# os20_newenc.net
KiCad netlist of a schematic drawn in EAGLE
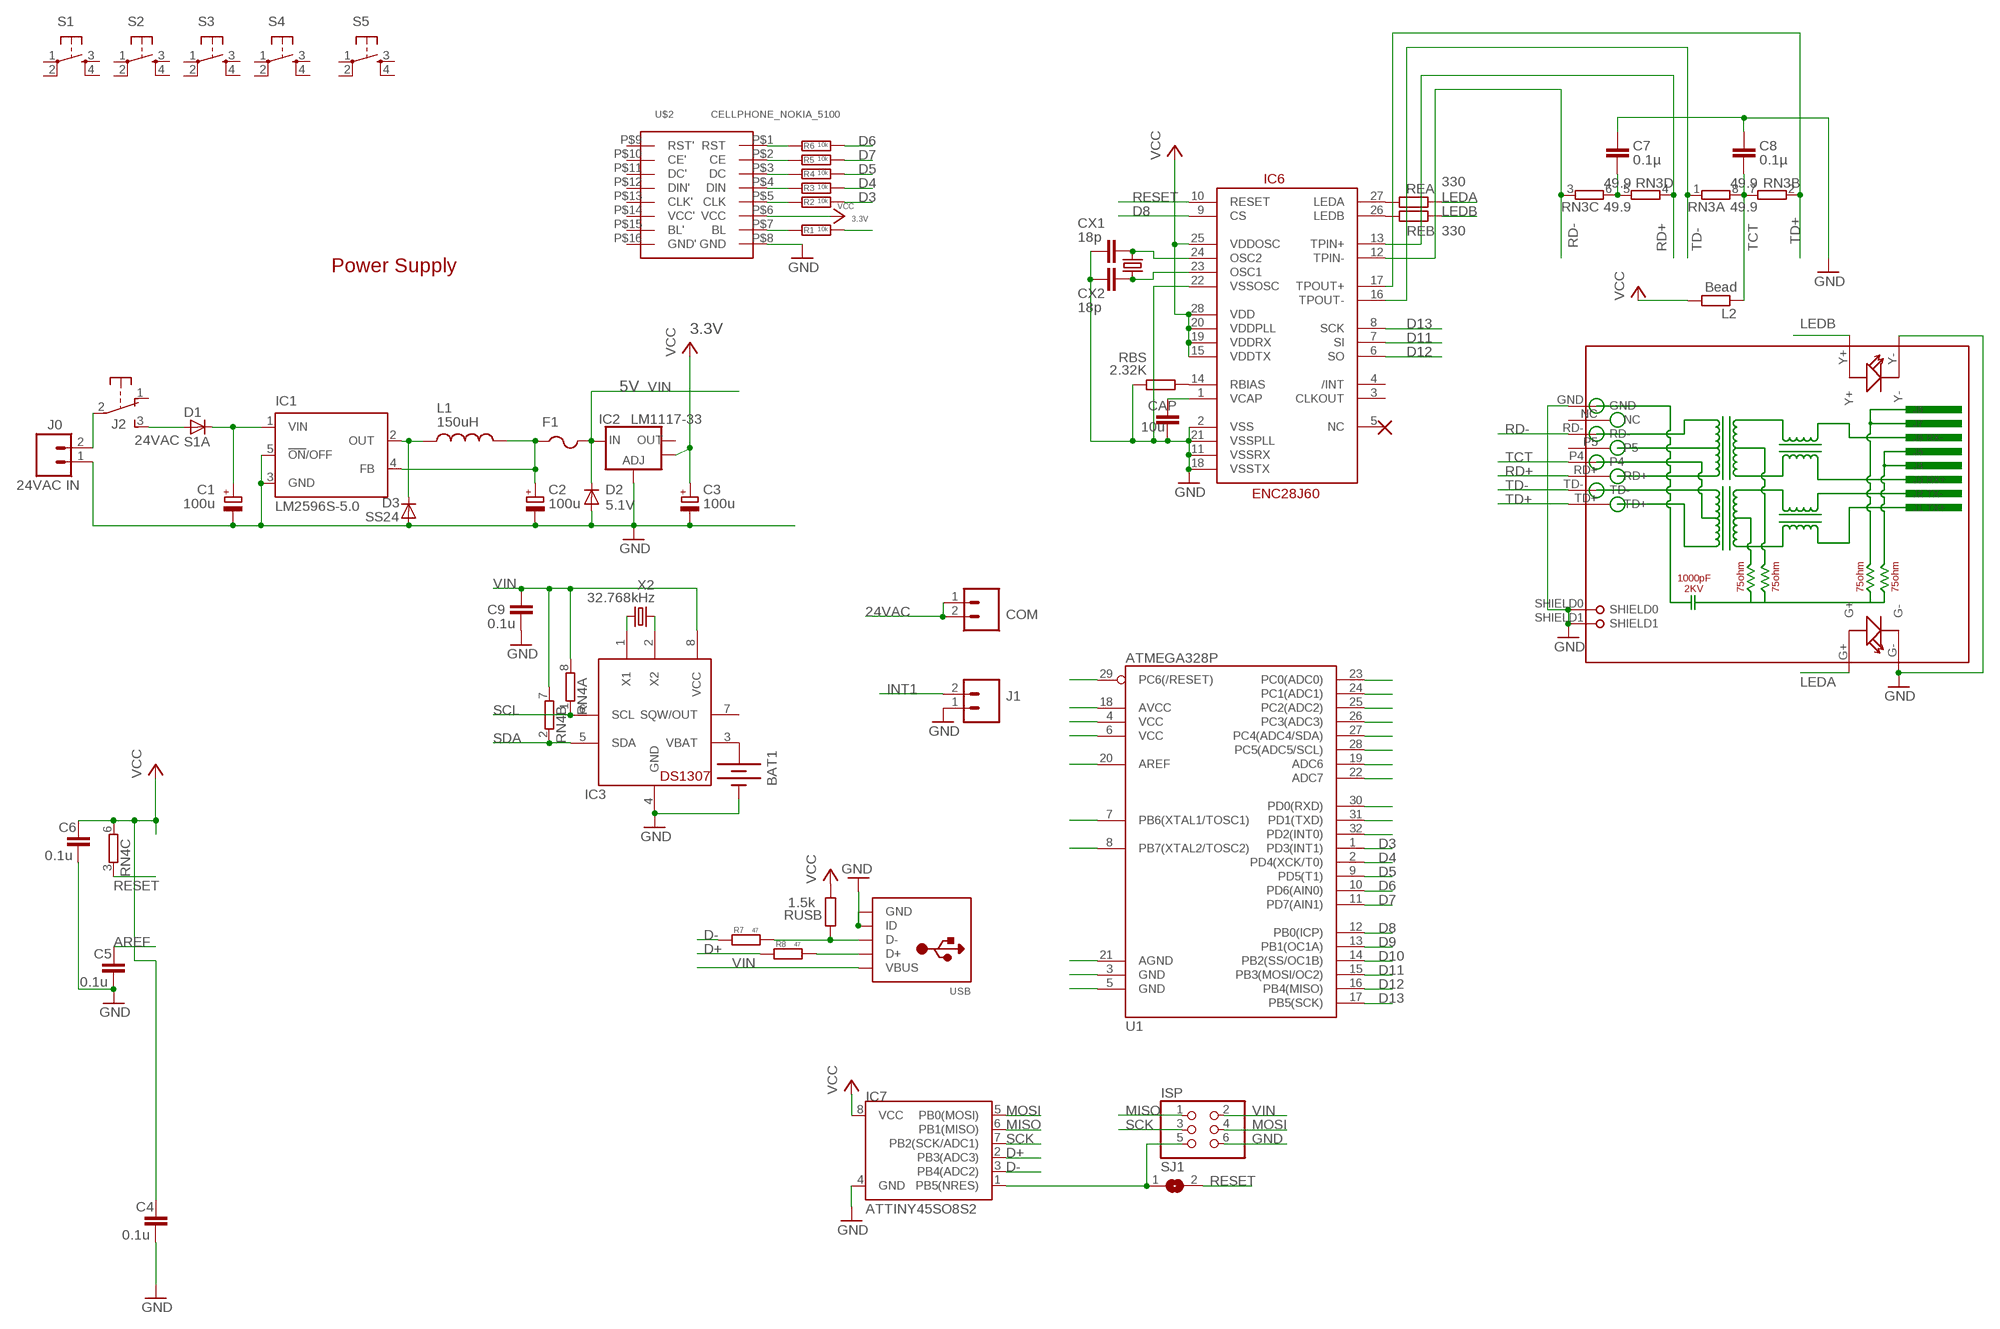
[diagram p0: schematic, sheet 1]

(export (version "E")
  (design (tool "Eeschema 10.0.6"))
  (components
    (comp (ref "BAT1")
      (value "BATTERYBATTERY_12MM_SMT")
      (footprint "eagle-import:BATTCON_12MM_SMT")
      (libsource (lib "eagle-import") (part "BATTERYBATTERY_12MM_SMT"))
    )
    (comp (ref "C1")
      (value "100u")
      (footprint "eagle-import:E3,5-8")
      (libsource (lib "eagle-import") (part "CPOL-EUE3.5-8"))
    )
    (comp (ref "C2")
      (value "100u")
      (footprint "eagle-import:PANASONIC_D")
      (libsource (lib "eagle-import") (part "CPOL-EUD"))
    )
    (comp (ref "C3")
      (value "100u")
      (footprint "eagle-import:PANASONIC_D")
      (libsource (lib "eagle-import") (part "CPOL-EUD"))
    )
    (comp (ref "C4")
      (value "0.1u")
      (footprint "eagle-import:C0805")
      (libsource (lib "eagle-import") (part "C-EUC0805"))
    )
    (comp (ref "C5")
      (value "0.1u")
      (footprint "eagle-import:C0805")
      (libsource (lib "eagle-import") (part "C-EUC0805"))
    )
    (comp (ref "C6")
      (value "0.1u")
      (footprint "eagle-import:C0805")
      (libsource (lib "eagle-import") (part "C-EUC0805"))
    )
    (comp (ref "C7")
      (value "0.1µ")
      (footprint "eagle-import:C0805")
      (libsource (lib "eagle-import") (part "resistor_C-EUC0805"))
    )
    (comp (ref "C8")
      (value "0.1µ")
      (footprint "eagle-import:C0805")
      (libsource (lib "eagle-import") (part "resistor_C-EUC0805"))
    )
    (comp (ref "C9")
      (value "0.1u")
      (footprint "eagle-import:C0805")
      (libsource (lib "eagle-import") (part "C-EUC0805"))
    )
    (comp (ref "CAP")
      (value "10u")
      (footprint "eagle-import:C0805")
      (libsource (lib "eagle-import") (part "resistor_C-EUC0805"))
    )
    (comp (ref "COM")
      (value "M025MM")
      (footprint "eagle-import:SCREWTERMINAL-5MM-2")
      (libsource (lib "eagle-import") (part "M025MM"))
    )
    (comp (ref "CX1")
      (value "18p")
      (footprint "eagle-import:C0805")
      (libsource (lib "eagle-import") (part "resistor_C-EUC0805"))
    )
    (comp (ref "CX2")
      (value "18p")
      (footprint "eagle-import:C0805")
      (libsource (lib "eagle-import") (part "resistor_C-EUC0805"))
    )
    (comp (ref "D1")
      (value "S1A")
      (footprint "eagle-import:DO-214AC")
      (libsource (lib "eagle-import") (part "DIODE-DO-214AC"))
    )
    (comp (ref "D2")
      (value "5.1V")
      (footprint "eagle-import:MINIMELF")
      (libsource (lib "eagle-import") (part "DIODE-MINIMELF"))
    )
    (comp (ref "D3")
      (value "SS24")
      (footprint "eagle-import:DO-214AC")
      (libsource (lib "eagle-import") (part "DIODE-DO-214AC"))
    )
    (comp (ref "F1")
      (value "PTCFUSE-1812")
      (footprint "eagle-import:1812")
      (libsource (lib "eagle-import") (part "PTCFUSE-1812"))
    )
    (comp (ref "IC1")
      (value "LM2596S-5.0")
      (footprint "eagle-import:TO263-5")
      (fields (field (name "MF") "NATIONAL SEMICONDUCTOR") (field (name "MPN") "LM2596S-ADJ/NOPB"))
      (libsource (lib "eagle-import") (part "LM2596S"))
    )
    (comp (ref "IC2")
      (value "LM1117-33")
      (footprint "eagle-import:SOT223")
      (libsource (lib "eagle-import") (part "V_REG_LM1117SOT223"))
    )
    (comp (ref "IC3")
      (value "DS1307")
      (footprint "eagle-import:SO08")
      (libsource (lib "eagle-import") (part "DS1307SOIC"))
    )
    (comp (ref "IC6")
      (value "ENC28J60")
      (footprint "eagle-import:SSOP28DB")
      (libsource (lib "eagle-import") (part "ENC28J60"))
    )
    (comp (ref "IC7")
      (value "ATTINY45SO8S2")
      (footprint "eagle-import:SO8S2")
      (libsource (lib "eagle-import") (part "ATTINY45SO8S2"))
    )
    (comp (ref "ISP")
      (value "PINHD-2X3")
      (footprint "eagle-import:2X03")
      (libsource (lib "eagle-import") (part "PINHD-2X3"))
    )
    (comp (ref "J0")
      (value "24VAC IN")
      (footprint "eagle-import:SCREWTERMINAL-5MM-2")
      (libsource (lib "eagle-import") (part "M025MM"))
    )
    (comp (ref "J1")
      (value "M025MM")
      (footprint "eagle-import:SCREWTERMINAL-5MM-2")
      (libsource (lib "eagle-import") (part "M025MM"))
    )
    (comp (ref "J2")
      (value "EG1206")
      (footprint "eagle-import:EG1206")
      (libsource (lib "eagle-import") (part "EG1206"))
    )
    (comp (ref "L1")
      (value "150uH")
      (footprint "eagle-import:CDRH125")
      (libsource (lib "eagle-import") (part "INDUCTORPWR"))
    )
    (comp (ref "L2")
      (value "Bead")
      (footprint "eagle-import:R0805")
      (libsource (lib "eagle-import") (part "R-EU_R0805"))
    )
    (comp (ref "R1")
      (value "10k")
      (footprint "eagle-import:R0805")
      (libsource (lib "eagle-import") (part "R-EU_R0805"))
    )
    (comp (ref "R2")
      (value "10k")
      (footprint "eagle-import:R0805")
      (libsource (lib "eagle-import") (part "R-EU_R0805"))
    )
    (comp (ref "R3")
      (value "10k")
      (footprint "eagle-import:R0805")
      (libsource (lib "eagle-import") (part "R-EU_R0805"))
    )
    (comp (ref "R4")
      (value "10k")
      (footprint "eagle-import:R0805")
      (libsource (lib "eagle-import") (part "R-EU_R0805"))
    )
    (comp (ref "R5")
      (value "10k")
      (footprint "eagle-import:R0805")
      (libsource (lib "eagle-import") (part "R-EU_R0805"))
    )
    (comp (ref "R6")
      (value "10k")
      (footprint "eagle-import:R0805")
      (libsource (lib "eagle-import") (part "R-EU_R0805"))
    )
    (comp (ref "R7")
      (value "47")
      (footprint "eagle-import:R0805")
      (libsource (lib "eagle-import") (part "R-EU_R0805"))
    )
    (comp (ref "R8")
      (value "47")
      (footprint "eagle-import:R0805")
      (libsource (lib "eagle-import") (part "R-EU_R0805"))
    )
    (comp (ref "RBS")
      (value "2.32K")
      (footprint "eagle-import:R0805")
      (libsource (lib "eagle-import") (part "R-EU_R0805"))
    )
    (comp (ref "REA")
      (value "330")
      (footprint "eagle-import:R0805")
      (libsource (lib "eagle-import") (part "R-EU_R0805"))
    )
    (comp (ref "REB")
      (value "330")
      (footprint "eagle-import:R0805")
      (libsource (lib "eagle-import") (part "R-EU_R0805"))
    )
    (comp (ref "RJ45")
      (value "HR911105A")
      (footprint "eagle-import:HR911105A")
      (libsource (lib "eagle-import") (part "HR911105A"))
    )
    (comp (ref "RN3")
      (value "49.9")
      (footprint "eagle-import:EXB38V")
      (libsource (lib "eagle-import") (part "4R-NEXB38V"))
    )
    (comp (ref "RN4")
      (value "4R-NEXB38V")
      (footprint "eagle-import:EXB38V")
      (libsource (lib "eagle-import") (part "4R-NEXB38V"))
    )
    (comp (ref "RUSB")
      (value "1.5k")
      (footprint "eagle-import:R0805")
      (libsource (lib "eagle-import") (part "R-EU_R0805"))
    )
    (comp (ref "S1")
      (value "TAC_SWITCHPTH")
      (footprint "eagle-import:TACTILE-PTH")
      (libsource (lib "eagle-import") (part "TAC_SWITCHPTH"))
    )
    (comp (ref "S2")
      (value "TAC_SWITCHPTH")
      (footprint "eagle-import:TACTILE-PTH")
      (libsource (lib "eagle-import") (part "TAC_SWITCHPTH"))
    )
    (comp (ref "S3")
      (value "TAC_SWITCHPTH")
      (footprint "eagle-import:TACTILE-PTH")
      (libsource (lib "eagle-import") (part "TAC_SWITCHPTH"))
    )
    (comp (ref "S4")
      (value "TAC_SWITCHPTH")
      (footprint "eagle-import:TACTILE-PTH")
      (libsource (lib "eagle-import") (part "TAC_SWITCHPTH"))
    )
    (comp (ref "S5")
      (value "TAC_SWITCHPTH")
      (footprint "eagle-import:TACTILE-PTH")
      (libsource (lib "eagle-import") (part "TAC_SWITCHPTH"))
    )
    (comp (ref "SJ1") (value "SJ") (footprint "eagle-import:SJ") (libsource (lib "eagle-import") (part "SJ")))
    (comp (ref "U$2")
      (value "CELLPHONE_NOKIA_5100")
      (footprint "eagle-import:CELLPHONE_NOKIA_5100_SPARKFUN")
      (libsource (lib "eagle-import") (part "CELLPHONE_NOKIA_5100"))
    )
    (comp (ref "U1")
      (value "ATMEGA328P")
      (footprint "eagle-import:TQFP32-08")
      (libsource (lib "eagle-import") (part "ATMEGA328_SMT"))
    )
    (comp (ref "USB")
      (value "USBMOLEX")
      (footprint "eagle-import:USB-MINIB-THM-MOLEX")
      (libsource (lib "eagle-import") (part "USBMOLEX"))
    )
    (comp (ref "X1")
      (value "25MHz")
      (footprint "eagle-import:HC49US")
      (libsource (lib "eagle-import") (part "CRYSTALHC49US"))
    )
    (comp (ref "X2")
      (value "32.768kHz")
      (footprint "eagle-import:TC26H")
      (libsource (lib "eagle-import") (part "crystal_CRYSTALTC26H"))
    )
  )
  (nets
    (net (code "1") (name "/24VAC") (class "Default")
      (node (ref "COM") (pin "1") (pinfunction "1_1") (pintype "passive"))
      (node (ref "COM") (pin "2") (pinfunction "2_2") (pintype "passive"))
      (node (ref "D1") (pin "A") (pinfunction "A_A") (pintype "passive"))
      (node (ref "J2") (pin "3") (pinfunction "S_3") (pintype "passive"))
    )
    (net (code "2") (name "/AREF") (class "Default")
      (node (ref "C5") (pin "1") (pinfunction "1_1") (pintype "passive"))
    )
    (net (code "3") (name "/D+") (class "Default")
      (node (ref "IC7") (pin "2") (pinfunction "PB3(ADC3)_2") (pintype "bidirectional"))
      (node (ref "R8") (pin "1") (pinfunction "1_1") (pintype "passive"))
    )
    (net (code "4") (name "/D-") (class "Default")
      (node (ref "IC7") (pin "3") (pinfunction "PB4(ADC2)_3") (pintype "bidirectional"))
      (node (ref "R7") (pin "1") (pinfunction "1_1") (pintype "passive"))
    )
    (net (code "5") (name "/D3") (class "Default")
      (node (ref "R2") (pin "2") (pinfunction "2_2") (pintype "passive"))
      (node (ref "U1") (pin "1") (pinfunction "PD3(INT1)_1") (pintype "bidirectional"))
    )
    (net (code "6") (name "/D4") (class "Default")
      (node (ref "R3") (pin "2") (pinfunction "2_2") (pintype "passive"))
      (node (ref "U1") (pin "2") (pinfunction "PD4(XCK/T0)_2") (pintype "bidirectional"))
    )
    (net (code "7") (name "/D5") (class "Default")
      (node (ref "R4") (pin "2") (pinfunction "2_2") (pintype "passive"))
      (node (ref "U1") (pin "9") (pinfunction "PD5(T1)_9") (pintype "bidirectional"))
    )
    (net (code "8") (name "/D6") (class "Default")
      (node (ref "R6") (pin "2") (pinfunction "2_2") (pintype "passive"))
      (node (ref "U1") (pin "10") (pinfunction "PD6(AIN0)_10") (pintype "bidirectional"))
    )
    (net (code "9") (name "/D7") (class "Default")
      (node (ref "R5") (pin "2") (pinfunction "2_2") (pintype "passive"))
      (node (ref "U1") (pin "11") (pinfunction "PD7(AIN1)_11") (pintype "bidirectional"))
    )
    (net (code "10") (name "/D8") (class "Default")
      (node (ref "IC6") (pin "9") (pinfunction "CS_9") (pintype "bidirectional"))
      (node (ref "U1") (pin "12") (pinfunction "PB0(ICP)_12") (pintype "bidirectional"))
    )
    (net (code "11") (name "/D9") (class "Default")
      (node (ref "U1") (pin "13") (pinfunction "PB1(OC1A)_13") (pintype "bidirectional"))
    )
    (net (code "12") (name "/D10") (class "Default")
      (node (ref "U1") (pin "14") (pinfunction "PB2(SS/OC1B)_14") (pintype "bidirectional"))
    )
    (net (code "13") (name "/D11") (class "Default")
      (node (ref "IC6") (pin "7") (pinfunction "SI_7") (pintype "bidirectional"))
      (node (ref "U1") (pin "15") (pinfunction "PB3(MOSI/OC2)_15") (pintype "bidirectional"))
    )
    (net (code "14") (name "/D12") (class "Default")
      (node (ref "IC6") (pin "6") (pinfunction "SO_6") (pintype "bidirectional"))
      (node (ref "U1") (pin "16") (pinfunction "PB4(MISO)_16") (pintype "bidirectional"))
    )
    (net (code "15") (name "/D13") (class "Default")
      (node (ref "IC6") (pin "8") (pinfunction "SCK_8") (pintype "bidirectional"))
      (node (ref "U1") (pin "17") (pinfunction "PB5(SCK)_17") (pintype "bidirectional"))
    )
    (net (code "16") (name "/INT1") (class "Default")
      (node (ref "J1") (pin "2") (pinfunction "2_2") (pintype "passive"))
    )
    (net (code "17") (name "/LEDA") (class "Default")
      (node (ref "REA") (pin "2") (pinfunction "2_2") (pintype "passive"))
      (node (ref "RJ45") (pin "G+") (pinfunction "G+_G+") (pintype "bidirectional"))
    )
    (net (code "18") (name "/LEDB") (class "Default")
      (node (ref "REB") (pin "2") (pinfunction "2_2") (pintype "passive"))
      (node (ref "RJ45") (pin "Y+") (pinfunction "Y+_Y+") (pintype "bidirectional"))
    )
    (net (code "19") (name "/MISO") (class "Default")
      (node (ref "IC7") (pin "6") (pinfunction "PB1(MISO)_6") (pintype "bidirectional"))
      (node (ref "ISP") (pin "1") (pinfunction "1_1") (pintype "passive"))
    )
    (net (code "20") (name "/MOSI") (class "Default")
      (node (ref "IC7") (pin "5") (pinfunction "PB0(MOSI)_5") (pintype "bidirectional"))
      (node (ref "ISP") (pin "4") (pinfunction "4_4") (pintype "passive"))
    )
    (net (code "21") (name "/RD+") (class "Default")
      (node (ref "IC6") (pin "13") (pinfunction "TPIN+_13") (pintype "bidirectional"))
      (node (ref "RJ45") (pin "RD+") (pinfunction "RD+_RD+") (pintype "bidirectional"))
      (node (ref "RN3") (pin "4") (pinfunction "1_4") (pintype "passive"))
    )
    (net (code "22") (name "/RD-") (class "Default")
      (node (ref "IC6") (pin "12") (pinfunction "TPIN-_12") (pintype "bidirectional"))
      (node (ref "RJ45") (pin "RD-") (pinfunction "RD-_RD-") (pintype "bidirectional"))
      (node (ref "RN3") (pin "3") (pinfunction "1_3") (pintype "passive"))
    )
    (net (code "23") (name "/RESET") (class "Default")
      (node (ref "IC6") (pin "10") (pinfunction "RESET_10") (pintype "bidirectional"))
      (node (ref "RN4") (pin "3") (pinfunction "1_3") (pintype "passive"))
      (node (ref "SJ1") (pin "2") (pinfunction "2_2") (pintype "passive"))
    )
    (net (code "24") (name "/SCK") (class "Default")
      (node (ref "IC7") (pin "7") (pinfunction "PB2(SCK/ADC1)_7") (pintype "bidirectional"))
      (node (ref "ISP") (pin "3") (pinfunction "3_3") (pintype "passive"))
    )
    (net (code "25") (name "/SCL") (class "Default")
      (node (ref "IC3") (pin "6") (pinfunction "SCL_6") (pintype "bidirectional"))
      (node (ref "RN4") (pin "1") (pinfunction "1_1") (pintype "passive"))
    )
    (net (code "26") (name "/SDA") (class "Default")
      (node (ref "IC3") (pin "5") (pinfunction "SDA_5") (pintype "bidirectional"))
      (node (ref "RN4") (pin "2") (pinfunction "1_2") (pintype "passive"))
    )
    (net (code "27") (name "/TCT") (class "Default")
      (node (ref "C8") (pin "2") (pinfunction "2_2") (pintype "passive"))
      (node (ref "L2") (pin "1") (pinfunction "1_1") (pintype "passive"))
      (node (ref "RJ45") (pin "P4") (pinfunction "P4_P4") (pintype "bidirectional"))
      (node (ref "RN3") (pin "7") (pinfunction "2_7") (pintype "passive"))
      (node (ref "RN3") (pin "8") (pinfunction "2_8") (pintype "passive"))
    )
    (net (code "28") (name "/TD+") (class "Default")
      (node (ref "IC6") (pin "17") (pinfunction "TPOUT+_17") (pintype "bidirectional"))
      (node (ref "RJ45") (pin "TD+") (pinfunction "TD+_TD+") (pintype "bidirectional"))
      (node (ref "RN3") (pin "2") (pinfunction "1_2") (pintype "passive"))
    )
    (net (code "29") (name "/TD-") (class "Default")
      (node (ref "IC6") (pin "16") (pinfunction "TPOUT-_16") (pintype "bidirectional"))
      (node (ref "RJ45") (pin "TD-") (pinfunction "TD-_TD-") (pintype "bidirectional"))
      (node (ref "RN3") (pin "1") (pinfunction "1_1") (pintype "passive"))
    )
    (net (code "30") (name "/VIN") (class "Default")
      (node (ref "C9") (pin "1") (pinfunction "1_1") (pintype "passive"))
      (node (ref "D2") (pin "C") (pinfunction "C_C") (pintype "passive"))
      (node (ref "F1") (pin "2") (pinfunction "2_2") (pintype "passive"))
      (node (ref "IC2") (pin "3") (pinfunction "IN_3") (pintype "input"))
      (node (ref "IC3") (pin "8") (pinfunction "VCC_8") (pintype "power_in"))
      (node (ref "ISP") (pin "2") (pinfunction "2_2") (pintype "passive"))
      (node (ref "RN4") (pin "7") (pinfunction "2_7") (pintype "passive"))
      (node (ref "RN4") (pin "8") (pinfunction "2_8") (pintype "passive"))
      (node (ref "USB") (pin "VBUS") (pinfunction "VBUS_VBUS") (pintype "power_in"))
    )
    (net (code "31") (name "GND") (class "Default")
      (node (ref "BAT1") (pin "P$1") (pinfunction "-_P$1") (pintype "power_in"))
      (node (ref "C1") (pin "-") (pinfunction "-_-") (pintype "passive"))
      (node (ref "C2") (pin "-") (pinfunction "-_-") (pintype "passive"))
      (node (ref "C3") (pin "-") (pinfunction "-_-") (pintype "passive"))
      (node (ref "C4") (pin "2") (pinfunction "2_2") (pintype "passive"))
      (node (ref "C5") (pin "2") (pinfunction "2_2") (pintype "passive"))
      (node (ref "C6") (pin "2") (pinfunction "2_2") (pintype "passive"))
      (node (ref "C7") (pin "1") (pinfunction "1_1") (pintype "passive"))
      (node (ref "C8") (pin "1") (pinfunction "1_1") (pintype "passive"))
      (node (ref "C9") (pin "2") (pinfunction "2_2") (pintype "passive"))
      (node (ref "CAP") (pin "2") (pinfunction "2_2") (pintype "passive"))
      (node (ref "CX1") (pin "2") (pinfunction "2_2") (pintype "passive"))
      (node (ref "CX2") (pin "2") (pinfunction "2_2") (pintype "passive"))
      (node (ref "D2") (pin "A") (pinfunction "A_A") (pintype "passive"))
      (node (ref "D3") (pin "A") (pinfunction "A_A") (pintype "passive"))
      (node (ref "IC1") (pin "3") (pinfunction "GND_3") (pintype "power_in"))
      (node (ref "IC1") (pin "5") (pinfunction "~{ON}/OFF_5") (pintype "input"))
      (node (ref "IC2") (pin "1") (pinfunction "ADJ_1") (pintype "input"))
      (node (ref "IC3") (pin "4") (pinfunction "GND_4") (pintype "power_in"))
      (node (ref "IC6") (pin "11") (pinfunction "VSSRX_11") (pintype "bidirectional"))
      (node (ref "IC6") (pin "18") (pinfunction "VSSTX_18") (pintype "bidirectional"))
      (node (ref "IC6") (pin "2") (pinfunction "VSS_2") (pintype "bidirectional"))
      (node (ref "IC6") (pin "21") (pinfunction "VSSPLL_21") (pintype "bidirectional"))
      (node (ref "IC6") (pin "22") (pinfunction "VSSOSC_22") (pintype "bidirectional"))
      (node (ref "IC7") (pin "4") (pinfunction "GND_4") (pintype "bidirectional"))
      (node (ref "ISP") (pin "6") (pinfunction "6_6") (pintype "passive"))
      (node (ref "J0") (pin "1") (pinfunction "1_1") (pintype "passive"))
      (node (ref "J1") (pin "1") (pinfunction "1_1") (pintype "passive"))
      (node (ref "RBS") (pin "1") (pinfunction "1_1") (pintype "passive"))
      (node (ref "RJ45") (pin "G-") (pinfunction "G-_G-") (pintype "bidirectional"))
      (node (ref "RJ45") (pin "GND") (pinfunction "GND_GND") (pintype "bidirectional"))
      (node (ref "RJ45") (pin "SHIELD0") (pinfunction "SHIELD0_SHIELD0") (pintype "bidirectional"))
      (node (ref "RJ45") (pin "SHIELD1") (pinfunction "SHIELD1_SHIELD1") (pintype "bidirectional"))
      (node (ref "RJ45") (pin "Y-") (pinfunction "Y-_Y-") (pintype "bidirectional"))
      (node (ref "U$2") (pin "P$8") (pinfunction "GND_P$8") (pintype "bidirectional"))
      (node (ref "USB") (pin "GND") (pinfunction "GND_GND") (pintype "power_in"))
      (node (ref "USB") (pin "ID") (pinfunction "ID_ID") (pintype "bidirectional"))
    )
    (net (code "32") (name "Net-(BAT1-+)") (class "Default")
      (node (ref "BAT1") (pin "P$2") (pinfunction "+_P$2") (pintype "power_in"))
      (node (ref "IC3") (pin "3") (pinfunction "VBAT_3") (pintype "power_in"))
    )
    (net (code "33") (name "Net-(IC1-FB)") (class "Default")
      (node (ref "C2") (pin "+") (pinfunction "+_+") (pintype "passive"))
      (node (ref "F1") (pin "1") (pinfunction "1_1") (pintype "passive"))
      (node (ref "IC1") (pin "4") (pinfunction "FB_4") (pintype "input"))
      (node (ref "L1") (pin "2") (pinfunction "2_2") (pintype "passive"))
    )
    (net (code "34") (name "Net-(IC1-OUT)") (class "Default")
      (node (ref "D3") (pin "C") (pinfunction "C_C") (pintype "passive"))
      (node (ref "IC1") (pin "2") (pinfunction "OUT_2") (pintype "output"))
      (node (ref "L1") (pin "1") (pinfunction "1_1") (pintype "passive"))
    )
    (net (code "35") (name "Net-(IC1-VIN)") (class "Default")
      (node (ref "C1") (pin "+") (pinfunction "+_+") (pintype "passive"))
      (node (ref "D1") (pin "C") (pinfunction "C_C") (pintype "passive"))
      (node (ref "IC1") (pin "1") (pinfunction "VIN_1") (pintype "input"))
    )
    (net (code "36") (name "Net-(IC3-X1)") (class "Default")
      (node (ref "IC3") (pin "1") (pinfunction "X1_1") (pintype "passive"))
      (node (ref "X2") (pin "2") (pinfunction "2_2") (pintype "passive"))
    )
    (net (code "37") (name "Net-(IC3-X2)") (class "Default")
      (node (ref "IC3") (pin "2") (pinfunction "X2_2") (pintype "passive"))
      (node (ref "X2") (pin "1") (pinfunction "1_1") (pintype "passive"))
    )
    (net (code "38") (name "Net-(IC6-LEDA)") (class "Default")
      (node (ref "IC6") (pin "27") (pinfunction "LEDA_27") (pintype "bidirectional"))
      (node (ref "REA") (pin "1") (pinfunction "1_1") (pintype "passive"))
    )
    (net (code "39") (name "Net-(IC6-LEDB)") (class "Default")
      (node (ref "IC6") (pin "26") (pinfunction "LEDB_26") (pintype "bidirectional"))
      (node (ref "REB") (pin "1") (pinfunction "1_1") (pintype "passive"))
    )
    (net (code "40") (name "Net-(IC6-OSC1)") (class "Default")
      (node (ref "CX2") (pin "1") (pinfunction "1_1") (pintype "passive"))
      (node (ref "IC6") (pin "23") (pinfunction "OSC1_23") (pintype "bidirectional"))
      (node (ref "X1") (pin "1") (pinfunction "1_1") (pintype "passive"))
    )
    (net (code "41") (name "Net-(IC6-OSC2)") (class "Default")
      (node (ref "CX1") (pin "1") (pinfunction "1_1") (pintype "passive"))
      (node (ref "IC6") (pin "24") (pinfunction "OSC2_24") (pintype "bidirectional"))
      (node (ref "X1") (pin "2") (pinfunction "2_2") (pintype "passive"))
    )
    (net (code "42") (name "Net-(IC6-RBIAS)") (class "Default")
      (node (ref "IC6") (pin "14") (pinfunction "RBIAS_14") (pintype "bidirectional"))
      (node (ref "RBS") (pin "2") (pinfunction "2_2") (pintype "passive"))
    )
    (net (code "43") (name "Net-(IC6-VCAP)") (class "Default")
      (node (ref "CAP") (pin "1") (pinfunction "1_1") (pintype "passive"))
      (node (ref "IC6") (pin "1") (pinfunction "VCAP_1") (pintype "bidirectional"))
    )
    (net (code "44") (name "Net-(IC7-PB5(NRES))") (class "Default")
      (node (ref "IC7") (pin "1") (pinfunction "PB5(NRES)_1") (pintype "bidirectional"))
      (node (ref "ISP") (pin "5") (pinfunction "5_5") (pintype "passive"))
      (node (ref "SJ1") (pin "1") (pinfunction "1_1") (pintype "passive"))
    )
    (net (code "45") (name "Net-(J2-P)") (class "Default")
      (node (ref "J0") (pin "2") (pinfunction "2_2") (pintype "passive"))
      (node (ref "J2") (pin "2") (pinfunction "P_2") (pintype "passive"))
    )
    (net (code "46") (name "Net-(R7-Pad2)") (class "Default")
      (node (ref "R7") (pin "2") (pinfunction "2_2") (pintype "passive"))
      (node (ref "RUSB") (pin "1") (pinfunction "1_1") (pintype "passive"))
      (node (ref "USB") (pin "D-") (pinfunction "D-_D-") (pintype "bidirectional"))
    )
    (net (code "47") (name "Net-(R8-Pad2)") (class "Default")
      (node (ref "R8") (pin "2") (pinfunction "2_2") (pintype "passive"))
      (node (ref "USB") (pin "D+") (pinfunction "D+_D+") (pintype "bidirectional"))
    )
    (net (code "48") (name "Net-(RN3C-2)") (class "Default")
      (node (ref "C7") (pin "2") (pinfunction "2_2") (pintype "passive"))
      (node (ref "RN3") (pin "5") (pinfunction "2_5") (pintype "passive"))
      (node (ref "RN3") (pin "6") (pinfunction "2_6") (pintype "passive"))
    )
    (net (code "49") (name "Net-(U$2-BL)") (class "Default")
      (node (ref "R1") (pin "1") (pinfunction "1_1") (pintype "passive"))
      (node (ref "U$2") (pin "P$7") (pinfunction "BL_P$7") (pintype "bidirectional"))
    )
    (net (code "50") (name "Net-(U$2-CE)") (class "Default")
      (node (ref "R5") (pin "1") (pinfunction "1_1") (pintype "passive"))
      (node (ref "U$2") (pin "P$2") (pinfunction "CE_P$2") (pintype "bidirectional"))
    )
    (net (code "51") (name "Net-(U$2-CLK)") (class "Default")
      (node (ref "R2") (pin "1") (pinfunction "1_1") (pintype "passive"))
      (node (ref "U$2") (pin "P$5") (pinfunction "CLK_P$5") (pintype "bidirectional"))
    )
    (net (code "52") (name "Net-(U$2-DC)") (class "Default")
      (node (ref "R4") (pin "1") (pinfunction "1_1") (pintype "passive"))
      (node (ref "U$2") (pin "P$3") (pinfunction "DC_P$3") (pintype "bidirectional"))
    )
    (net (code "53") (name "Net-(U$2-DIN)") (class "Default")
      (node (ref "R3") (pin "1") (pinfunction "1_1") (pintype "passive"))
      (node (ref "U$2") (pin "P$4") (pinfunction "DIN_P$4") (pintype "bidirectional"))
    )
    (net (code "54") (name "Net-(U$2-RST)") (class "Default")
      (node (ref "R6") (pin "1") (pinfunction "1_1") (pintype "passive"))
      (node (ref "U$2") (pin "P$1") (pinfunction "RST_P$1") (pintype "bidirectional"))
    )
    (net (code "55") (name "VCC") (class "Default")
      (node (ref "C3") (pin "+") (pinfunction "+_+") (pintype "passive"))
      (node (ref "C4") (pin "1") (pinfunction "1_1") (pintype "passive"))
      (node (ref "C6") (pin "1") (pinfunction "1_1") (pintype "passive"))
      (node (ref "IC2") (pin "4") (pinfunction "OUT_4") (pintype "bidirectional"))
      (node (ref "IC6") (pin "15") (pinfunction "VDDTX_15") (pintype "bidirectional"))
      (node (ref "IC6") (pin "19") (pinfunction "VDDRX_19") (pintype "bidirectional"))
      (node (ref "IC6") (pin "20") (pinfunction "VDDPLL_20") (pintype "bidirectional"))
      (node (ref "IC6") (pin "25") (pinfunction "VDDOSC_25") (pintype "bidirectional"))
      (node (ref "IC6") (pin "28") (pinfunction "VDD_28") (pintype "bidirectional"))
      (node (ref "IC7") (pin "8") (pinfunction "VCC_8") (pintype "bidirectional"))
      (node (ref "L2") (pin "2") (pinfunction "2_2") (pintype "passive"))
      (node (ref "RN4") (pin "6") (pinfunction "2_6") (pintype "passive"))
      (node (ref "RUSB") (pin "2") (pinfunction "2_2") (pintype "passive"))
      (node (ref "U$2") (pin "P$6") (pinfunction "VCC_P$6") (pintype "bidirectional"))
    )
    (net (code "56") (name "unconnected-(IC2-OUT-Pad2)") (class "Default")
      (node (ref "IC2") (pin "2") (pinfunction "OUT_2") (pintype "bidirectional"))
    )
    (net (code "57") (name "unconnected-(IC3-SQW{slash}OUT-Pad7)") (class "Default")
      (node (ref "IC3") (pin "7") (pinfunction "SQW/OUT_7") (pintype "bidirectional"))
    )
    (net (code "58") (name "unconnected-(IC6-CLKOUT-Pad3)") (class "Default")
      (node (ref "IC6") (pin "3") (pinfunction "CLKOUT_3") (pintype "bidirectional"))
    )
    (net (code "59") (name "unconnected-(IC6-NC-Pad5)") (class "Default")
      (node (ref "IC6") (pin "5") (pinfunction "NC_5") (pintype "bidirectional"))
    )
    (net (code "60") (name "unconnected-(IC6-{slash}INT-Pad4)") (class "Default")
      (node (ref "IC6") (pin "4") (pinfunction "/INT_4") (pintype "bidirectional"))
    )
    (net (code "61") (name "unconnected-(J2-O-Pad1)") (class "Default")
      (node (ref "J2") (pin "1") (pinfunction "O_1") (pintype "passive"))
    )
    (net (code "62") (name "unconnected-(R1-Pad2)") (class "Default")
      (node (ref "R1") (pin "2") (pinfunction "2_2") (pintype "passive"))
    )
    (net (code "63") (name "unconnected-(RJ45-PadNC)") (class "Default")
      (node (ref "RJ45") (pin "NC") (pinfunction "NC_NC") (pintype "bidirectional"))
    )
    (net (code "64") (name "unconnected-(RJ45-PadP5)") (class "Default")
      (node (ref "RJ45") (pin "P5") (pinfunction "P5_P5") (pintype "bidirectional"))
    )
    (net (code "65") (name "unconnected-(S1-Pad1)") (class "Default")
      (node (ref "S1") (pin "1") (pinfunction "1_1") (pintype "passive"))
    )
    (net (code "66") (name "unconnected-(S1-Pad2)") (class "Default")
      (node (ref "S1") (pin "2") (pinfunction "2_2") (pintype "passive"))
    )
    (net (code "67") (name "unconnected-(S1-Pad3)") (class "Default")
      (node (ref "S1") (pin "3") (pinfunction "3_3") (pintype "passive"))
    )
    (net (code "68") (name "unconnected-(S1-Pad4)") (class "Default")
      (node (ref "S1") (pin "4") (pinfunction "4_4") (pintype "passive"))
    )
    (net (code "69") (name "unconnected-(S2-Pad1)") (class "Default")
      (node (ref "S2") (pin "1") (pinfunction "1_1") (pintype "passive"))
    )
    (net (code "70") (name "unconnected-(S2-Pad2)") (class "Default")
      (node (ref "S2") (pin "2") (pinfunction "2_2") (pintype "passive"))
    )
    (net (code "71") (name "unconnected-(S2-Pad3)") (class "Default")
      (node (ref "S2") (pin "3") (pinfunction "3_3") (pintype "passive"))
    )
    (net (code "72") (name "unconnected-(S2-Pad4)") (class "Default")
      (node (ref "S2") (pin "4") (pinfunction "4_4") (pintype "passive"))
    )
    (net (code "73") (name "unconnected-(S3-Pad1)") (class "Default")
      (node (ref "S3") (pin "1") (pinfunction "1_1") (pintype "passive"))
    )
    (net (code "74") (name "unconnected-(S3-Pad2)") (class "Default")
      (node (ref "S3") (pin "2") (pinfunction "2_2") (pintype "passive"))
    )
    (net (code "75") (name "unconnected-(S3-Pad3)") (class "Default")
      (node (ref "S3") (pin "3") (pinfunction "3_3") (pintype "passive"))
    )
    (net (code "76") (name "unconnected-(S3-Pad4)") (class "Default")
      (node (ref "S3") (pin "4") (pinfunction "4_4") (pintype "passive"))
    )
    (net (code "77") (name "unconnected-(S4-Pad1)") (class "Default")
      (node (ref "S4") (pin "1") (pinfunction "1_1") (pintype "passive"))
    )
    (net (code "78") (name "unconnected-(S4-Pad2)") (class "Default")
      (node (ref "S4") (pin "2") (pinfunction "2_2") (pintype "passive"))
    )
    (net (code "79") (name "unconnected-(S4-Pad3)") (class "Default")
      (node (ref "S4") (pin "3") (pinfunction "3_3") (pintype "passive"))
    )
    (net (code "80") (name "unconnected-(S4-Pad4)") (class "Default")
      (node (ref "S4") (pin "4") (pinfunction "4_4") (pintype "passive"))
    )
    (net (code "81") (name "unconnected-(S5-Pad1)") (class "Default")
      (node (ref "S5") (pin "1") (pinfunction "1_1") (pintype "passive"))
    )
    (net (code "82") (name "unconnected-(S5-Pad2)") (class "Default")
      (node (ref "S5") (pin "2") (pinfunction "2_2") (pintype "passive"))
    )
    (net (code "83") (name "unconnected-(S5-Pad3)") (class "Default")
      (node (ref "S5") (pin "3") (pinfunction "3_3") (pintype "passive"))
    )
    (net (code "84") (name "unconnected-(S5-Pad4)") (class "Default")
      (node (ref "S5") (pin "4") (pinfunction "4_4") (pintype "passive"))
    )
    (net (code "85") (name "unconnected-(U$2-BL'-PadP$15)") (class "Default")
      (node (ref "U$2") (pin "P$15") (pinfunction "BL'_P$15") (pintype "bidirectional"))
    )
    (net (code "86") (name "unconnected-(U$2-CE'-PadP$10)") (class "Default")
      (node (ref "U$2") (pin "P$10") (pinfunction "CE'_P$10") (pintype "bidirectional"))
    )
    (net (code "87") (name "unconnected-(U$2-CLK'-PadP$13)") (class "Default")
      (node (ref "U$2") (pin "P$13") (pinfunction "CLK'_P$13") (pintype "bidirectional"))
    )
    (net (code "88") (name "unconnected-(U$2-DC'-PadP$11)") (class "Default")
      (node (ref "U$2") (pin "P$11") (pinfunction "DC'_P$11") (pintype "bidirectional"))
    )
    (net (code "89") (name "unconnected-(U$2-DIN'-PadP$12)") (class "Default")
      (node (ref "U$2") (pin "P$12") (pinfunction "DIN'_P$12") (pintype "bidirectional"))
    )
    (net (code "90") (name "unconnected-(U$2-GND'-PadP$16)") (class "Default")
      (node (ref "U$2") (pin "P$16") (pinfunction "GND'_P$16") (pintype "bidirectional"))
    )
    (net (code "91") (name "unconnected-(U$2-RST'-PadP$9)") (class "Default")
      (node (ref "U$2") (pin "P$9") (pinfunction "RST'_P$9") (pintype "bidirectional"))
    )
    (net (code "92") (name "unconnected-(U$2-VCC'-PadP$14)") (class "Default")
      (node (ref "U$2") (pin "P$14") (pinfunction "VCC'_P$14") (pintype "bidirectional"))
    )
    (net (code "93") (name "unconnected-(U1-ADC6-Pad19)") (class "Default")
      (node (ref "U1") (pin "19") (pinfunction "ADC6_19") (pintype "bidirectional"))
    )
    (net (code "94") (name "unconnected-(U1-ADC7-Pad22)") (class "Default")
      (node (ref "U1") (pin "22") (pinfunction "ADC7_22") (pintype "bidirectional"))
    )
    (net (code "95") (name "unconnected-(U1-AGND-Pad21)") (class "Default")
      (node (ref "U1") (pin "21") (pinfunction "AGND_21") (pintype "bidirectional"))
    )
    (net (code "96") (name "unconnected-(U1-AREF-Pad20)") (class "Default")
      (node (ref "U1") (pin "20") (pinfunction "AREF_20") (pintype "bidirectional"))
    )
    (net (code "97") (name "unconnected-(U1-AVCC-Pad18)") (class "Default")
      (node (ref "U1") (pin "18") (pinfunction "AVCC_18") (pintype "bidirectional"))
    )
    (net (code "98") (name "unconnected-(U1-GND-Pad3)") (class "Default")
      (node (ref "U1") (pin "3") (pinfunction "GND_3") (pintype "bidirectional"))
    )
    (net (code "99") (name "unconnected-(U1-GND-Pad5)") (class "Default")
      (node (ref "U1") (pin "5") (pinfunction "GND_5") (pintype "bidirectional"))
    )
    (net (code "100") (name "unconnected-(U1-PB6(XTAL1{slash}TOSC1)-Pad7)") (class "Default")
      (node (ref "U1") (pin "7") (pinfunction "PB6(XTAL1/TOSC1)_7") (pintype "bidirectional"))
    )
    (net (code "101") (name "unconnected-(U1-PB7(XTAL2{slash}TOSC2)-Pad8)") (class "Default")
      (node (ref "U1") (pin "8") (pinfunction "PB7(XTAL2/TOSC2)_8") (pintype "bidirectional"))
    )
    (net (code "102") (name "unconnected-(U1-PC0(ADC0)-Pad23)") (class "Default")
      (node (ref "U1") (pin "23") (pinfunction "PC0(ADC0)_23") (pintype "bidirectional"))
    )
    (net (code "103") (name "unconnected-(U1-PC1(ADC1)-Pad24)") (class "Default")
      (node (ref "U1") (pin "24") (pinfunction "PC1(ADC1)_24") (pintype "bidirectional"))
    )
    (net (code "104") (name "unconnected-(U1-PC2(ADC2)-Pad25)") (class "Default")
      (node (ref "U1") (pin "25") (pinfunction "PC2(ADC2)_25") (pintype "bidirectional"))
    )
    (net (code "105") (name "unconnected-(U1-PC3(ADC3)-Pad26)") (class "Default")
      (node (ref "U1") (pin "26") (pinfunction "PC3(ADC3)_26") (pintype "bidirectional"))
    )
    (net (code "106") (name "unconnected-(U1-PC4(ADC4{slash}SDA)-Pad27)") (class "Default")
      (node (ref "U1") (pin "27") (pinfunction "PC4(ADC4/SDA)_27") (pintype "bidirectional"))
    )
    (net (code "107") (name "unconnected-(U1-PC5(ADC5{slash}SCL)-Pad28)") (class "Default")
      (node (ref "U1") (pin "28") (pinfunction "PC5(ADC5/SCL)_28") (pintype "bidirectional"))
    )
    (net (code "108") (name "unconnected-(U1-PC6({slash}RESET)-Pad29)") (class "Default")
      (node (ref "U1") (pin "29") (pinfunction "PC6(/RESET)_29") (pintype "bidirectional"))
    )
    (net (code "109") (name "unconnected-(U1-PD0(RXD)-Pad30)") (class "Default")
      (node (ref "U1") (pin "30") (pinfunction "PD0(RXD)_30") (pintype "bidirectional"))
    )
    (net (code "110") (name "unconnected-(U1-PD1(TXD)-Pad31)") (class "Default")
      (node (ref "U1") (pin "31") (pinfunction "PD1(TXD)_31") (pintype "bidirectional"))
    )
    (net (code "111") (name "unconnected-(U1-PD2(INT0)-Pad32)") (class "Default")
      (node (ref "U1") (pin "32") (pinfunction "PD2(INT0)_32") (pintype "bidirectional"))
    )
    (net (code "112") (name "unconnected-(U1-VCC-Pad4)") (class "Default")
      (node (ref "U1") (pin "4") (pinfunction "VCC_4") (pintype "bidirectional"))
    )
    (net (code "113") (name "unconnected-(U1-VCC-Pad6)") (class "Default")
      (node (ref "U1") (pin "6") (pinfunction "VCC_6") (pintype "bidirectional"))
    )
  )
)
